# BeamMini.net
KiCad netlist of a schematic drawn in EAGLE
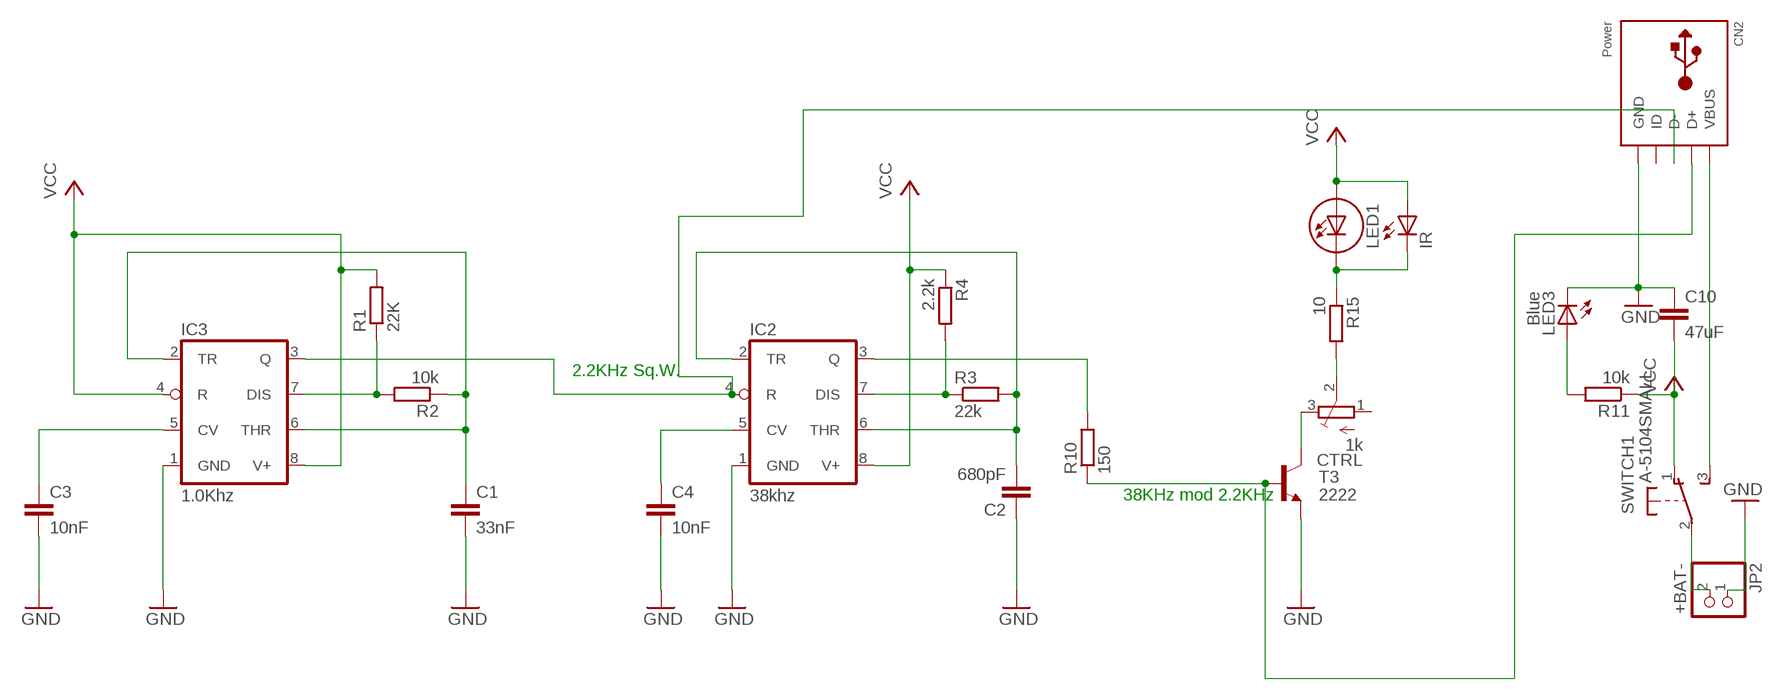
[diagram p0: schematic, sheet 1]

(export (version "E")
  (design (tool "Eeschema 10.0.6"))
  (components
    (comp (ref "C1")
      (value "33nF")
      (footprint "eagle-import:C0805")
      (libsource (lib "eagle-import") (part "C-EUC0805"))
    )
    (comp (ref "C2")
      (value "680pF")
      (footprint "eagle-import:C0805")
      (libsource (lib "eagle-import") (part "C-EUC0805"))
    )
    (comp (ref "C3")
      (value "10nF")
      (footprint "eagle-import:C0805")
      (libsource (lib "eagle-import") (part "C-EUC0805"))
    )
    (comp (ref "C4")
      (value "10nF")
      (footprint "eagle-import:C0805")
      (libsource (lib "eagle-import") (part "C-EUC0805"))
    )
    (comp (ref "C10")
      (value "47uF")
      (footprint "eagle-import:C0805")
      (libsource (lib "eagle-import") (part "C-EUC0805"))
    )
    (comp (ref "CN2")
      (value "Power")
      (footprint "eagle-import:USB-MINIB")
      (libsource (lib "eagle-import") (part "USBMINIB"))
    )
    (comp (ref "CTRL")
      (value "1k")
      (footprint "eagle-import:TC33X")
      (libsource (lib "eagle-import") (part "TRIMPOTTC33X"))
    )
    (comp (ref "IC2")
      (value "38khz")
      (footprint "eagle-import:SO08")
      (libsource (lib "eagle-import") (part "555DNE"))
    )
    (comp (ref "IC3")
      (value "1.0Khz")
      (footprint "eagle-import:SO08")
      (libsource (lib "eagle-import") (part "555DNE"))
    )
    (comp (ref "IR")
      (value "LED5MM")
      (footprint "eagle-import:LED5MM")
      (libsource (lib "eagle-import") (part "LED5MM"))
    )
    (comp (ref "JP2")
      (value "+BAT-")
      (footprint "eagle-import:1X02M")
      (libsource (lib "eagle-import") (part "PINHD-1X02_2.00"))
    )
    (comp (ref "LED1")
      (value "LUXEON-2")
      (footprint "eagle-import:LUXEON-2")
      (libsource (lib "eagle-import") (part "LUXEON-2"))
    )
    (comp (ref "LED3")
      (value "Blue")
      (footprint "eagle-import:CHIP-LED0805")
      (libsource (lib "eagle-import") (part "LEDCHIP-LED0805"))
    )
    (comp (ref "R1")
      (value "22K")
      (footprint "eagle-import:M0805")
      (libsource (lib "eagle-import") (part "R-EU_M0805"))
    )
    (comp (ref "R2")
      (value "10k")
      (footprint "eagle-import:M0805")
      (libsource (lib "eagle-import") (part "R-EU_M0805"))
    )
    (comp (ref "R3")
      (value "22k")
      (footprint "eagle-import:M0805")
      (libsource (lib "eagle-import") (part "R-EU_M0805"))
    )
    (comp (ref "R4")
      (value "2.2k")
      (footprint "eagle-import:M0805")
      (libsource (lib "eagle-import") (part "R-EU_M0805"))
    )
    (comp (ref "R10")
      (value "150")
      (footprint "eagle-import:M0805")
      (libsource (lib "eagle-import") (part "R-EU_M0805"))
    )
    (comp (ref "R11")
      (value "10k")
      (footprint "eagle-import:M0805")
      (libsource (lib "eagle-import") (part "R-EU_M0805"))
    )
    (comp (ref "R15")
      (value "10")
      (footprint "eagle-import:R0805")
      (libsource (lib "eagle-import") (part "R-EU_R0805"))
    )
    (comp (ref "SWITCH")
      (value "A-5104SMALL")
      (footprint "eagle-import:A-5104-SMALL")
      (libsource (lib "eagle-import") (part "A-5104SMALL"))
    )
    (comp (ref "T3")
      (value "2222")
      (footprint "eagle-import:SOT23")
      (libsource (lib "eagle-import") (part "TRANSISTOR_NPNSOT23"))
    )
  )
  (nets
    (net (code "1") (name "GND") (class "Default")
      (node (ref "C1") (pin "2") (pinfunction "2_2") (pintype "passive"))
      (node (ref "C10") (pin "1") (pinfunction "1_1") (pintype "passive"))
      (node (ref "C2") (pin "1") (pinfunction "1_1") (pintype "passive"))
      (node (ref "C3") (pin "2") (pinfunction "2_2") (pintype "passive"))
      (node (ref "C4") (pin "2") (pinfunction "2_2") (pintype "passive"))
      (node (ref "CN2") (pin "GND") (pinfunction "GND_GND") (pintype "power_in"))
      (node (ref "IC2") (pin "1") (pinfunction "GND_1") (pintype "power_in"))
      (node (ref "IC3") (pin "1") (pinfunction "GND_1") (pintype "power_in"))
      (node (ref "JP2") (pin "1") (pinfunction "1_1") (pintype "passive"))
      (node (ref "LED3") (pin "C") (pinfunction "C_C") (pintype "passive"))
      (node (ref "T3") (pin "2") (pinfunction "E_2") (pintype "passive"))
    )
    (net (code "2") (name "Net-(CTRL-E)") (class "Default")
      (node (ref "CTRL") (pin "3") (pinfunction "E_3") (pintype "passive"))
      (node (ref "T3") (pin "3") (pinfunction "C_3") (pintype "passive"))
    )
    (net (code "3") (name "Net-(CTRL-S)") (class "Default")
      (node (ref "CTRL") (pin "2") (pinfunction "S_2") (pintype "passive"))
      (node (ref "R15") (pin "2") (pinfunction "2_2") (pintype "passive"))
    )
    (net (code "4") (name "Net-(IC2-CV)") (class "Default")
      (node (ref "C4") (pin "1") (pinfunction "1_1") (pintype "passive"))
      (node (ref "IC2") (pin "5") (pinfunction "CV_5") (pintype "input"))
    )
    (net (code "5") (name "Net-(IC2-DIS)") (class "Default")
      (node (ref "IC2") (pin "7") (pinfunction "DIS_7") (pintype "input"))
      (node (ref "R3") (pin "1") (pinfunction "1_1") (pintype "passive"))
      (node (ref "R4") (pin "2") (pinfunction "2_2") (pintype "passive"))
    )
    (net (code "6") (name "Net-(IC2-Q)") (class "Default")
      (node (ref "IC2") (pin "3") (pinfunction "Q_3") (pintype "output"))
      (node (ref "R10") (pin "2") (pinfunction "2_2") (pintype "passive"))
    )
    (net (code "7") (name "Net-(IC2-R)") (class "Default")
      (node (ref "CN2") (pin "D-") (pinfunction "D-_D-") (pintype "bidirectional"))
      (node (ref "IC2") (pin "4") (pinfunction "R_4") (pintype "input"))
      (node (ref "IC3") (pin "3") (pinfunction "Q_3") (pintype "output"))
    )
    (net (code "8") (name "Net-(IC2-THR)") (class "Default")
      (node (ref "C2") (pin "2") (pinfunction "2_2") (pintype "passive"))
      (node (ref "IC2") (pin "2") (pinfunction "TR_2") (pintype "input"))
      (node (ref "IC2") (pin "6") (pinfunction "THR_6") (pintype "input"))
      (node (ref "R3") (pin "2") (pinfunction "2_2") (pintype "passive"))
    )
    (net (code "9") (name "Net-(IC3-CV)") (class "Default")
      (node (ref "C3") (pin "1") (pinfunction "1_1") (pintype "passive"))
      (node (ref "IC3") (pin "5") (pinfunction "CV_5") (pintype "input"))
    )
    (net (code "10") (name "Net-(IC3-DIS)") (class "Default")
      (node (ref "IC3") (pin "7") (pinfunction "DIS_7") (pintype "input"))
      (node (ref "R1") (pin "1") (pinfunction "1_1") (pintype "passive"))
      (node (ref "R2") (pin "2") (pinfunction "2_2") (pintype "passive"))
    )
    (net (code "11") (name "Net-(IC3-THR)") (class "Default")
      (node (ref "C1") (pin "1") (pinfunction "1_1") (pintype "passive"))
      (node (ref "IC3") (pin "2") (pinfunction "TR_2") (pintype "input"))
      (node (ref "IC3") (pin "6") (pinfunction "THR_6") (pintype "input"))
      (node (ref "R2") (pin "1") (pinfunction "1_1") (pintype "passive"))
    )
    (net (code "12") (name "Net-(IR-C)") (class "Default")
      (node (ref "IR") (pin "K") (pinfunction "C_K") (pintype "passive"))
      (node (ref "LED1") (pin "C") (pinfunction "C_C") (pintype "passive"))
      (node (ref "R15") (pin "1") (pinfunction "1_1") (pintype "passive"))
    )
    (net (code "13") (name "Net-(LED3-PadA)") (class "Default")
      (node (ref "LED3") (pin "A") (pinfunction "A_A") (pintype "passive"))
      (node (ref "R11") (pin "2") (pinfunction "2_2") (pintype "passive"))
    )
    (net (code "14") (name "Net-(SWITCHA-P)") (class "Default")
      (node (ref "JP2") (pin "2") (pinfunction "2_2") (pintype "passive"))
      (node (ref "SWITCH") (pin "2") (pinfunction "P_2") (pintype "passive"))
    )
    (net (code "15") (name "Net-(SWITCHA-S)") (class "Default")
      (node (ref "CN2") (pin "VBUS") (pinfunction "VBUS_VBUS") (pintype "power_in"))
      (node (ref "SWITCH") (pin "3") (pinfunction "S_3") (pintype "passive"))
    )
    (net (code "16") (name "Net-(T3-B)") (class "Default")
      (node (ref "CN2") (pin "D+") (pinfunction "D+_D+") (pintype "bidirectional"))
      (node (ref "R10") (pin "1") (pinfunction "1_1") (pintype "passive"))
      (node (ref "T3") (pin "1") (pinfunction "B_1") (pintype "passive"))
    )
    (net (code "17") (name "VCC") (class "Default")
      (node (ref "C10") (pin "2") (pinfunction "2_2") (pintype "passive"))
      (node (ref "IC2") (pin "8") (pinfunction "V+_8") (pintype "power_in"))
      (node (ref "IC3") (pin "4") (pinfunction "R_4") (pintype "input"))
      (node (ref "IC3") (pin "8") (pinfunction "V+_8") (pintype "power_in"))
      (node (ref "IR") (pin "A") (pinfunction "A_A") (pintype "passive"))
      (node (ref "LED1") (pin "A") (pinfunction "A_A") (pintype "passive"))
      (node (ref "R1") (pin "2") (pinfunction "2_2") (pintype "passive"))
      (node (ref "R11") (pin "1") (pinfunction "1_1") (pintype "passive"))
      (node (ref "R4") (pin "1") (pinfunction "1_1") (pintype "passive"))
      (node (ref "SWITCH") (pin "1") (pinfunction "O_1") (pintype "passive"))
    )
    (net (code "18") (name "unconnected-(CN2-PadID)") (class "Default")
      (node (ref "CN2") (pin "ID") (pinfunction "ID_ID") (pintype "bidirectional"))
    )
    (net (code "19") (name "unconnected-(CTRL-A-Pad1)") (class "Default")
      (node (ref "CTRL") (pin "1") (pinfunction "A_1") (pintype "passive"))
    )
  )
)
